# withjack.net
KiCad netlist of a schematic drawn in EAGLE
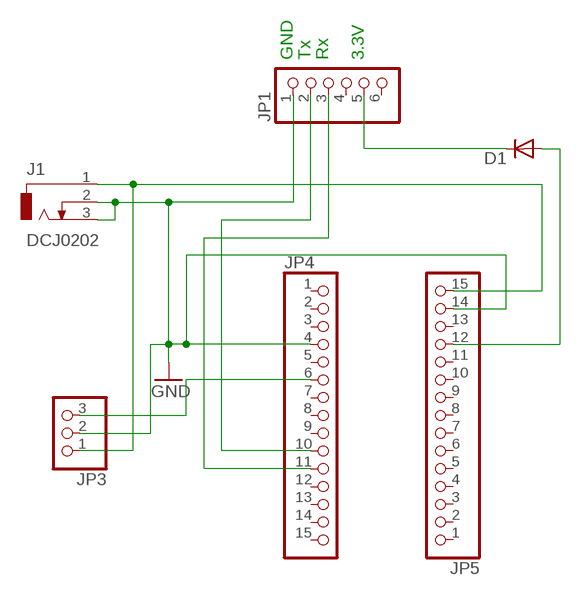
[diagram p0: schematic, sheet 1]

(export (version "E")
  (design (tool "Eeschema 10.0.6"))
  (components
    (comp (ref "D1")
      (value "1N4004")
      (footprint "eagle-import:DO41-10")
      (libsource (lib "eagle-import") (part "1N4004"))
    )
    (comp (ref "J1")
      (value "DCJ0202")
      (footprint "eagle-import:DCJ0202")
      (libsource (lib "eagle-import") (part "DCJ0202"))
    )
    (comp (ref "JP1")
      (value "PINHD-1X6")
      (footprint "eagle-import:1X06")
      (libsource (lib "eagle-import") (part "PINHD-1X6"))
    )
    (comp (ref "JP3")
      (value "PINHD-1X3")
      (footprint "eagle-import:1X03")
      (libsource (lib "eagle-import") (part "PINHD-1X3"))
    )
    (comp (ref "JP4")
      (value "PINHD-1X15")
      (footprint "eagle-import:1X15")
      (libsource (lib "eagle-import") (part "PINHD-1X15"))
    )
    (comp (ref "JP5")
      (value "PINHD-1X15")
      (footprint "eagle-import:1X15")
      (libsource (lib "eagle-import") (part "PINHD-1X15"))
    )
  )
  (nets
    (net (code "1") (name "GND") (class "Default")
      (node (ref "J1") (pin "2") (pinfunction "2_2") (pintype "passive"))
      (node (ref "J1") (pin "3") (pinfunction "3_3") (pintype "passive"))
      (node (ref "JP1") (pin "1") (pinfunction "1_1") (pintype "passive"))
      (node (ref "JP3") (pin "2") (pinfunction "2_2") (pintype "passive"))
      (node (ref "JP4") (pin "4") (pinfunction "4_4") (pintype "passive"))
      (node (ref "JP5") (pin "14") (pinfunction "14_14") (pintype "passive"))
    )
    (net (code "2") (name "Net-(D1-PadA)") (class "Default")
      (node (ref "D1") (pin "A") (pinfunction "A_A") (pintype "passive"))
      (node (ref "JP5") (pin "12") (pinfunction "12_12") (pintype "passive"))
    )
    (net (code "3") (name "Net-(D1-PadC)") (class "Default")
      (node (ref "D1") (pin "C") (pinfunction "C_C") (pintype "passive"))
      (node (ref "JP1") (pin "5") (pinfunction "5_5") (pintype "passive"))
    )
    (net (code "4") (name "Net-(J1-Pad1)") (class "Default")
      (node (ref "J1") (pin "1") (pinfunction "1_1") (pintype "passive"))
      (node (ref "JP3") (pin "1") (pinfunction "1_1") (pintype "passive"))
      (node (ref "JP5") (pin "15") (pinfunction "15_15") (pintype "passive"))
    )
    (net (code "5") (name "Net-(JP1-Pad2)") (class "Default")
      (node (ref "JP1") (pin "2") (pinfunction "2_2") (pintype "passive"))
      (node (ref "JP4") (pin "10") (pinfunction "10_10") (pintype "passive"))
    )
    (net (code "6") (name "Net-(JP1-Pad3)") (class "Default")
      (node (ref "JP1") (pin "3") (pinfunction "3_3") (pintype "passive"))
      (node (ref "JP4") (pin "11") (pinfunction "11_11") (pintype "passive"))
    )
    (net (code "7") (name "Net-(JP3-Pad3)") (class "Default")
      (node (ref "JP3") (pin "3") (pinfunction "3_3") (pintype "passive"))
      (node (ref "JP4") (pin "6") (pinfunction "6_6") (pintype "passive"))
    )
    (net (code "8") (name "unconnected-(JP1-Pad4)") (class "Default")
      (node (ref "JP1") (pin "4") (pinfunction "4_4") (pintype "passive"))
    )
    (net (code "9") (name "unconnected-(JP1-Pad6)") (class "Default")
      (node (ref "JP1") (pin "6") (pinfunction "6_6") (pintype "passive"))
    )
    (net (code "10") (name "unconnected-(JP4-Pad1)") (class "Default")
      (node (ref "JP4") (pin "1") (pinfunction "1_1") (pintype "passive"))
    )
    (net (code "11") (name "unconnected-(JP4-Pad2)") (class "Default")
      (node (ref "JP4") (pin "2") (pinfunction "2_2") (pintype "passive"))
    )
    (net (code "12") (name "unconnected-(JP4-Pad3)") (class "Default")
      (node (ref "JP4") (pin "3") (pinfunction "3_3") (pintype "passive"))
    )
    (net (code "13") (name "unconnected-(JP4-Pad5)") (class "Default")
      (node (ref "JP4") (pin "5") (pinfunction "5_5") (pintype "passive"))
    )
    (net (code "14") (name "unconnected-(JP4-Pad7)") (class "Default")
      (node (ref "JP4") (pin "7") (pinfunction "7_7") (pintype "passive"))
    )
    (net (code "15") (name "unconnected-(JP4-Pad8)") (class "Default")
      (node (ref "JP4") (pin "8") (pinfunction "8_8") (pintype "passive"))
    )
    (net (code "16") (name "unconnected-(JP4-Pad9)") (class "Default")
      (node (ref "JP4") (pin "9") (pinfunction "9_9") (pintype "passive"))
    )
    (net (code "17") (name "unconnected-(JP4-Pad12)") (class "Default")
      (node (ref "JP4") (pin "12") (pinfunction "12_12") (pintype "passive"))
    )
    (net (code "18") (name "unconnected-(JP4-Pad13)") (class "Default")
      (node (ref "JP4") (pin "13") (pinfunction "13_13") (pintype "passive"))
    )
    (net (code "19") (name "unconnected-(JP4-Pad14)") (class "Default")
      (node (ref "JP4") (pin "14") (pinfunction "14_14") (pintype "passive"))
    )
    (net (code "20") (name "unconnected-(JP4-Pad15)") (class "Default")
      (node (ref "JP4") (pin "15") (pinfunction "15_15") (pintype "passive"))
    )
    (net (code "21") (name "unconnected-(JP5-Pad1)") (class "Default")
      (node (ref "JP5") (pin "1") (pinfunction "1_1") (pintype "passive"))
    )
    (net (code "22") (name "unconnected-(JP5-Pad2)") (class "Default")
      (node (ref "JP5") (pin "2") (pinfunction "2_2") (pintype "passive"))
    )
    (net (code "23") (name "unconnected-(JP5-Pad3)") (class "Default")
      (node (ref "JP5") (pin "3") (pinfunction "3_3") (pintype "passive"))
    )
    (net (code "24") (name "unconnected-(JP5-Pad4)") (class "Default")
      (node (ref "JP5") (pin "4") (pinfunction "4_4") (pintype "passive"))
    )
    (net (code "25") (name "unconnected-(JP5-Pad5)") (class "Default")
      (node (ref "JP5") (pin "5") (pinfunction "5_5") (pintype "passive"))
    )
    (net (code "26") (name "unconnected-(JP5-Pad6)") (class "Default")
      (node (ref "JP5") (pin "6") (pinfunction "6_6") (pintype "passive"))
    )
    (net (code "27") (name "unconnected-(JP5-Pad7)") (class "Default")
      (node (ref "JP5") (pin "7") (pinfunction "7_7") (pintype "passive"))
    )
    (net (code "28") (name "unconnected-(JP5-Pad8)") (class "Default")
      (node (ref "JP5") (pin "8") (pinfunction "8_8") (pintype "passive"))
    )
    (net (code "29") (name "unconnected-(JP5-Pad9)") (class "Default")
      (node (ref "JP5") (pin "9") (pinfunction "9_9") (pintype "passive"))
    )
    (net (code "30") (name "unconnected-(JP5-Pad10)") (class "Default")
      (node (ref "JP5") (pin "10") (pinfunction "10_10") (pintype "passive"))
    )
    (net (code "31") (name "unconnected-(JP5-Pad11)") (class "Default")
      (node (ref "JP5") (pin "11") (pinfunction "11_11") (pintype "passive"))
    )
    (net (code "32") (name "unconnected-(JP5-Pad13)") (class "Default")
      (node (ref "JP5") (pin "13") (pinfunction "13_13") (pintype "passive"))
    )
  )
)
